# crawler_esp12.net
KiCad netlist of a schematic drawn in EAGLE
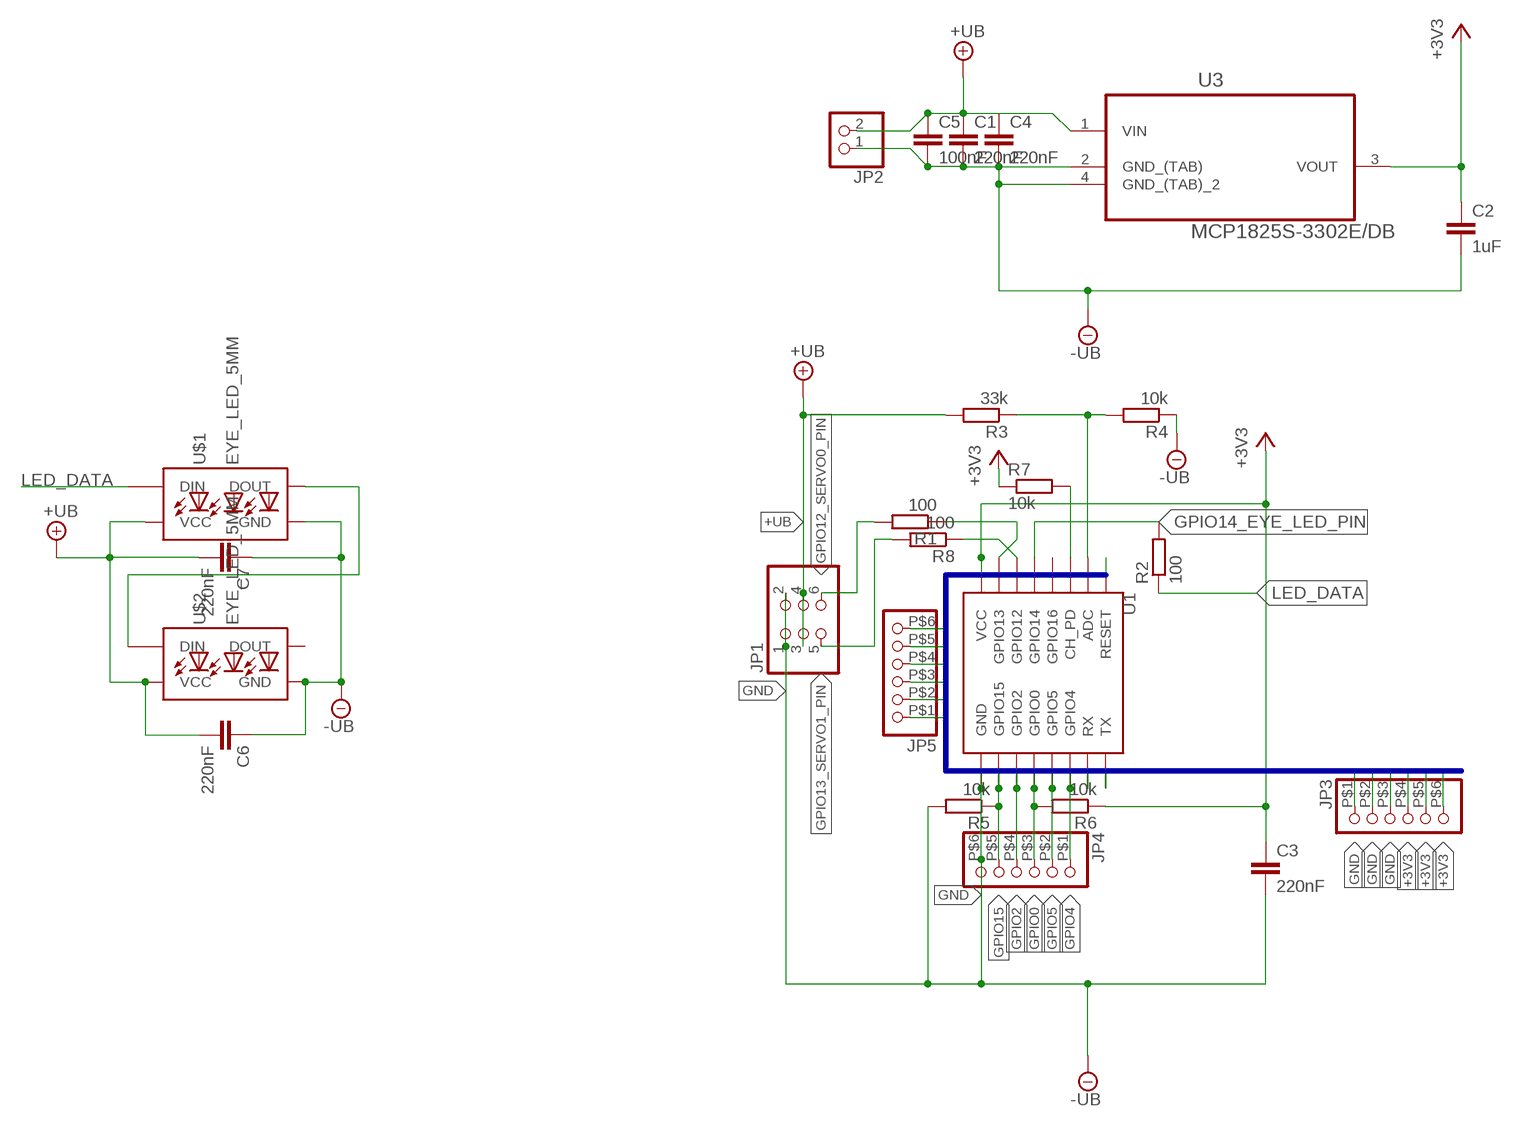
[diagram p0: schematic, sheet 1]

(export (version "E")
  (design (tool "Eeschema 10.0.6"))
  (components
    (comp (ref "C1")
      (value "220nF")
      (footprint "eagle-import:C0805")
      (libsource (lib "eagle-import") (part "C-EUC0805"))
    )
    (comp (ref "C2")
      (value "1uF")
      (footprint "eagle-import:C0805")
      (libsource (lib "eagle-import") (part "C-EUC0805"))
    )
    (comp (ref "C3")
      (value "220nF")
      (footprint "eagle-import:C0805")
      (libsource (lib "eagle-import") (part "C-EUC0805"))
    )
    (comp (ref "C4")
      (value "220nF")
      (footprint "eagle-import:C0805")
      (libsource (lib "eagle-import") (part "C-EUC0805"))
    )
    (comp (ref "C5")
      (value "100nF")
      (footprint "eagle-import:C0805")
      (libsource (lib "eagle-import") (part "C-EUC0805"))
    )
    (comp (ref "C6")
      (value "220nF")
      (footprint "eagle-import:C0805")
      (libsource (lib "eagle-import") (part "C-EUC0805"))
    )
    (comp (ref "C7")
      (value "220nF")
      (footprint "eagle-import:C0805")
      (libsource (lib "eagle-import") (part "C-EUC0805"))
    )
    (comp (ref "JP1")
      (value "PINHD-2X3")
      (footprint "eagle-import:2X03")
      (libsource (lib "eagle-import") (part "PINHD-2X3"))
    )
    (comp (ref "JP2")
      (value "PINHD-1X2")
      (footprint "eagle-import:1X02")
      (libsource (lib "eagle-import") (part "PINHD-1X2"))
    )
    (comp (ref "JP3")
      (value "PINHD-1X6SMD")
      (footprint "eagle-import:1X06_90_SMD")
      (libsource (lib "eagle-import") (part "PINHD-1X6SMD"))
    )
    (comp (ref "JP4")
      (value "PINHD-1X6SMD")
      (footprint "eagle-import:1X06_90_SMD")
      (libsource (lib "eagle-import") (part "PINHD-1X6SMD"))
    )
    (comp (ref "JP5")
      (value "PINHD-1X6SMD")
      (footprint "eagle-import:1X06_90_SMD")
      (libsource (lib "eagle-import") (part "PINHD-1X6SMD"))
    )
    (comp (ref "R1")
      (value "100")
      (footprint "eagle-import:R0805")
      (libsource (lib "eagle-import") (part "R-EU_R0805"))
    )
    (comp (ref "R2")
      (value "100")
      (footprint "eagle-import:R0805")
      (libsource (lib "eagle-import") (part "R-EU_R0805"))
    )
    (comp (ref "R3")
      (value "33k")
      (footprint "eagle-import:R0805")
      (libsource (lib "eagle-import") (part "R-EU_R0805"))
    )
    (comp (ref "R4")
      (value "10k")
      (footprint "eagle-import:R0805")
      (libsource (lib "eagle-import") (part "R-EU_R0805"))
    )
    (comp (ref "R5")
      (value "10k")
      (footprint "eagle-import:R0805")
      (libsource (lib "eagle-import") (part "R-EU_R0805"))
    )
    (comp (ref "R6")
      (value "10k")
      (footprint "eagle-import:R0805")
      (libsource (lib "eagle-import") (part "R-EU_R0805"))
    )
    (comp (ref "R7")
      (value "10k")
      (footprint "eagle-import:R0805")
      (libsource (lib "eagle-import") (part "R-EU_R0805"))
    )
    (comp (ref "R8")
      (value "100")
      (footprint "eagle-import:R0805")
      (libsource (lib "eagle-import") (part "R-EU_R0805"))
    )
    (comp (ref "U$1")
      (value "EYE_LED_5MM")
      (footprint "eagle-import:EYE_LED_5MM")
      (libsource (lib "eagle-import") (part "EYE_LED_5MM"))
    )
    (comp (ref "U$2")
      (value "EYE_LED_5MM")
      (footprint "eagle-import:EYE_LED_5MM")
      (libsource (lib "eagle-import") (part "EYE_LED_5MM"))
    )
    (comp (ref "U1")
      (value "ESP12SMD")
      (footprint "eagle-import:ESP12-SMD")
      (libsource (lib "eagle-import") (part "ESP12SMD"))
    )
    (comp (ref "U3")
      (value "MCP1825S-3302E/DB")
      (footprint "eagle-import:SOT230P700X180-4N")
      (libsource (lib "eagle-import") (part "MCP1825S-3302E/DB"))
    )
  )
  (nets
    (net (code "1") (name "+3V3") (class "Default")
      (node (ref "C2") (pin "1") (pinfunction "1_1") (pintype "passive"))
      (node (ref "C3") (pin "1") (pinfunction "1_1") (pintype "passive"))
      (node (ref "JP3") (pin "P$4") (pinfunction "4_P$4") (pintype "passive"))
      (node (ref "JP3") (pin "P$5") (pinfunction "5_P$5") (pintype "passive"))
      (node (ref "JP3") (pin "P$6") (pinfunction "6_P$6") (pintype "passive"))
      (node (ref "JP5") (pin "P$1") (pinfunction "1_P$1") (pintype "passive"))
      (node (ref "R6") (pin "1") (pinfunction "1_1") (pintype "passive"))
      (node (ref "R7") (pin "1") (pinfunction "1_1") (pintype "passive"))
      (node (ref "U1") (pin "VCC") (pinfunction "VCC_VCC") (pintype "bidirectional"))
      (node (ref "U3") (pin "3") (pinfunction "VOUT_3") (pintype "output"))
    )
    (net (code "2") (name "+UB") (class "Default")
      (node (ref "C1") (pin "1") (pinfunction "1_1") (pintype "passive"))
      (node (ref "C4") (pin "1") (pinfunction "1_1") (pintype "passive"))
      (node (ref "C5") (pin "1") (pinfunction "1_1") (pintype "passive"))
      (node (ref "C6") (pin "2") (pinfunction "2_2") (pintype "passive"))
      (node (ref "C7") (pin "2") (pinfunction "2_2") (pintype "passive"))
      (node (ref "JP1") (pin "3") (pinfunction "3_3") (pintype "passive"))
      (node (ref "JP1") (pin "4") (pinfunction "4_4") (pintype "passive"))
      (node (ref "JP2") (pin "2") (pinfunction "2_2") (pintype "passive"))
      (node (ref "R3") (pin "2") (pinfunction "2_2") (pintype "passive"))
      (node (ref "U$1") (pin "5V") (pinfunction "VCC_5V") (pintype "passive"))
      (node (ref "U$2") (pin "5V") (pinfunction "VCC_5V") (pintype "passive"))
      (node (ref "U3") (pin "1") (pinfunction "VIN_1") (pintype "input"))
    )
    (net (code "3") (name "/RESET") (class "Default")
      (node (ref "JP5") (pin "P$5") (pinfunction "5_P$5") (pintype "passive"))
      (node (ref "U1") (pin "RESET") (pinfunction "RESET_RESET") (pintype "bidirectional"))
    )
    (net (code "4") (name "/RX") (class "Default")
      (node (ref "JP5") (pin "P$4") (pinfunction "4_P$4") (pintype "passive"))
      (node (ref "U1") (pin "RXD0") (pinfunction "RX_RXD0") (pintype "bidirectional"))
    )
    (net (code "5") (name "/TX") (class "Default")
      (node (ref "JP5") (pin "P$3") (pinfunction "3_P$3") (pintype "passive"))
      (node (ref "U1") (pin "TXD0") (pinfunction "TX_TXD0") (pintype "bidirectional"))
    )
    (net (code "6") (name "GND") (class "Default")
      (node (ref "C1") (pin "2") (pinfunction "2_2") (pintype "passive"))
      (node (ref "C2") (pin "2") (pinfunction "2_2") (pintype "passive"))
      (node (ref "C3") (pin "2") (pinfunction "2_2") (pintype "passive"))
      (node (ref "C4") (pin "2") (pinfunction "2_2") (pintype "passive"))
      (node (ref "C5") (pin "2") (pinfunction "2_2") (pintype "passive"))
      (node (ref "C6") (pin "1") (pinfunction "1_1") (pintype "passive"))
      (node (ref "C7") (pin "1") (pinfunction "1_1") (pintype "passive"))
      (node (ref "JP1") (pin "1") (pinfunction "1_1") (pintype "passive"))
      (node (ref "JP1") (pin "2") (pinfunction "2_2") (pintype "passive"))
      (node (ref "JP2") (pin "1") (pinfunction "1_1") (pintype "passive"))
      (node (ref "JP3") (pin "P$1") (pinfunction "1_P$1") (pintype "passive"))
      (node (ref "JP3") (pin "P$2") (pinfunction "2_P$2") (pintype "passive"))
      (node (ref "JP3") (pin "P$3") (pinfunction "3_P$3") (pintype "passive"))
      (node (ref "JP4") (pin "P$6") (pinfunction "6_P$6") (pintype "passive"))
      (node (ref "JP5") (pin "P$6") (pinfunction "6_P$6") (pintype "passive"))
      (node (ref "R4") (pin "1") (pinfunction "1_1") (pintype "passive"))
      (node (ref "R5") (pin "2") (pinfunction "2_2") (pintype "passive"))
      (node (ref "U$1") (pin "GND") (pinfunction "GND_GND") (pintype "passive"))
      (node (ref "U$2") (pin "GND") (pinfunction "GND_GND") (pintype "passive"))
      (node (ref "U1") (pin "GND") (pinfunction "GND_GND") (pintype "bidirectional"))
      (node (ref "U3") (pin "2") (pinfunction "GND_(TAB)_2") (pintype "passive"))
      (node (ref "U3") (pin "4") (pinfunction "GND_(TAB)_2_4") (pintype "passive"))
    )
    (net (code "7") (name "GPIO0") (class "Default")
      (node (ref "JP4") (pin "P$3") (pinfunction "3_P$3") (pintype "passive"))
      (node (ref "JP5") (pin "P$2") (pinfunction "2_P$2") (pintype "passive"))
      (node (ref "R6") (pin "2") (pinfunction "2_2") (pintype "passive"))
      (node (ref "U1") (pin "GPIO0") (pinfunction "GPIO0_GPIO0") (pintype "bidirectional"))
    )
    (net (code "8") (name "GPIO2") (class "Default")
      (node (ref "JP4") (pin "P$4") (pinfunction "4_P$4") (pintype "passive"))
      (node (ref "U1") (pin "GPIO2") (pinfunction "GPIO2_GPIO2") (pintype "bidirectional"))
    )
    (net (code "9") (name "GPIO4") (class "Default")
      (node (ref "JP4") (pin "P$1") (pinfunction "1_P$1") (pintype "passive"))
      (node (ref "U1") (pin "GPIO4") (pinfunction "GPIO4_GPIO4") (pintype "bidirectional"))
    )
    (net (code "10") (name "GPIO5") (class "Default")
      (node (ref "JP4") (pin "P$2") (pinfunction "2_P$2") (pintype "passive"))
      (node (ref "U1") (pin "GPIO5") (pinfunction "GPIO5_GPIO5") (pintype "bidirectional"))
    )
    (net (code "11") (name "GPIO12_SERVO0_PIN") (class "Default")
      (node (ref "JP1") (pin "6") (pinfunction "6_6") (pintype "passive"))
      (node (ref "R1") (pin "2") (pinfunction "2_2") (pintype "passive"))
    )
    (net (code "12") (name "GPIO13_SERVO1_PIN") (class "Default")
      (node (ref "JP1") (pin "5") (pinfunction "5_5") (pintype "passive"))
      (node (ref "R8") (pin "2") (pinfunction "2_2") (pintype "passive"))
    )
    (net (code "13") (name "GPIO14_EYE_LED_PIN") (class "Default")
      (node (ref "R2") (pin "2") (pinfunction "2_2") (pintype "passive"))
      (node (ref "U1") (pin "GPIO14") (pinfunction "GPIO14_GPIO14") (pintype "bidirectional"))
    )
    (net (code "14") (name "GPIO15") (class "Default")
      (node (ref "JP4") (pin "P$5") (pinfunction "5_P$5") (pintype "passive"))
      (node (ref "R5") (pin "1") (pinfunction "1_1") (pintype "passive"))
      (node (ref "U1") (pin "GPIO15") (pinfunction "GPIO15_GPIO15") (pintype "bidirectional"))
    )
    (net (code "15") (name "LED_DATA") (class "Default")
      (node (ref "R2") (pin "1") (pinfunction "1_1") (pintype "passive"))
      (node (ref "U$1") (pin "DIN") (pinfunction "DIN_DIN") (pintype "input"))
    )
    (net (code "16") (name "Net-(R1-Pad1)") (class "Default")
      (node (ref "R1") (pin "1") (pinfunction "1_1") (pintype "passive"))
      (node (ref "U1") (pin "GPIO13") (pinfunction "GPIO13_GPIO13") (pintype "bidirectional"))
    )
    (net (code "17") (name "Net-(R3-Pad1)") (class "Default")
      (node (ref "R3") (pin "1") (pinfunction "1_1") (pintype "passive"))
      (node (ref "R4") (pin "2") (pinfunction "2_2") (pintype "passive"))
      (node (ref "U1") (pin "ADC") (pinfunction "ADC_ADC") (pintype "bidirectional"))
    )
    (net (code "18") (name "Net-(R7-Pad2)") (class "Default")
      (node (ref "R7") (pin "2") (pinfunction "2_2") (pintype "passive"))
      (node (ref "U1") (pin "CH_PD") (pinfunction "CH_PD_CH_PD") (pintype "bidirectional"))
    )
    (net (code "19") (name "Net-(R8-Pad1)") (class "Default")
      (node (ref "R8") (pin "1") (pinfunction "1_1") (pintype "passive"))
      (node (ref "U1") (pin "GPIO12") (pinfunction "GPIO12_GPIO12") (pintype "bidirectional"))
    )
    (net (code "20") (name "Net-(U$1-PadDOUT)") (class "Default")
      (node (ref "U$1") (pin "DOUT") (pinfunction "DOUT_DOUT") (pintype "output"))
      (node (ref "U$2") (pin "DIN") (pinfunction "DIN_DIN") (pintype "input"))
    )
    (net (code "21") (name "unconnected-(U$2-PadDOUT)") (class "Default")
      (node (ref "U$2") (pin "DOUT") (pinfunction "DOUT_DOUT") (pintype "output"))
    )
    (net (code "22") (name "unconnected-(U1-PadGPIO16)") (class "Default")
      (node (ref "U1") (pin "GPIO16") (pinfunction "GPIO16_GPIO16") (pintype "bidirectional"))
    )
  )
)
